# BSK4new.net
KiCad netlist of a schematic drawn in EAGLE
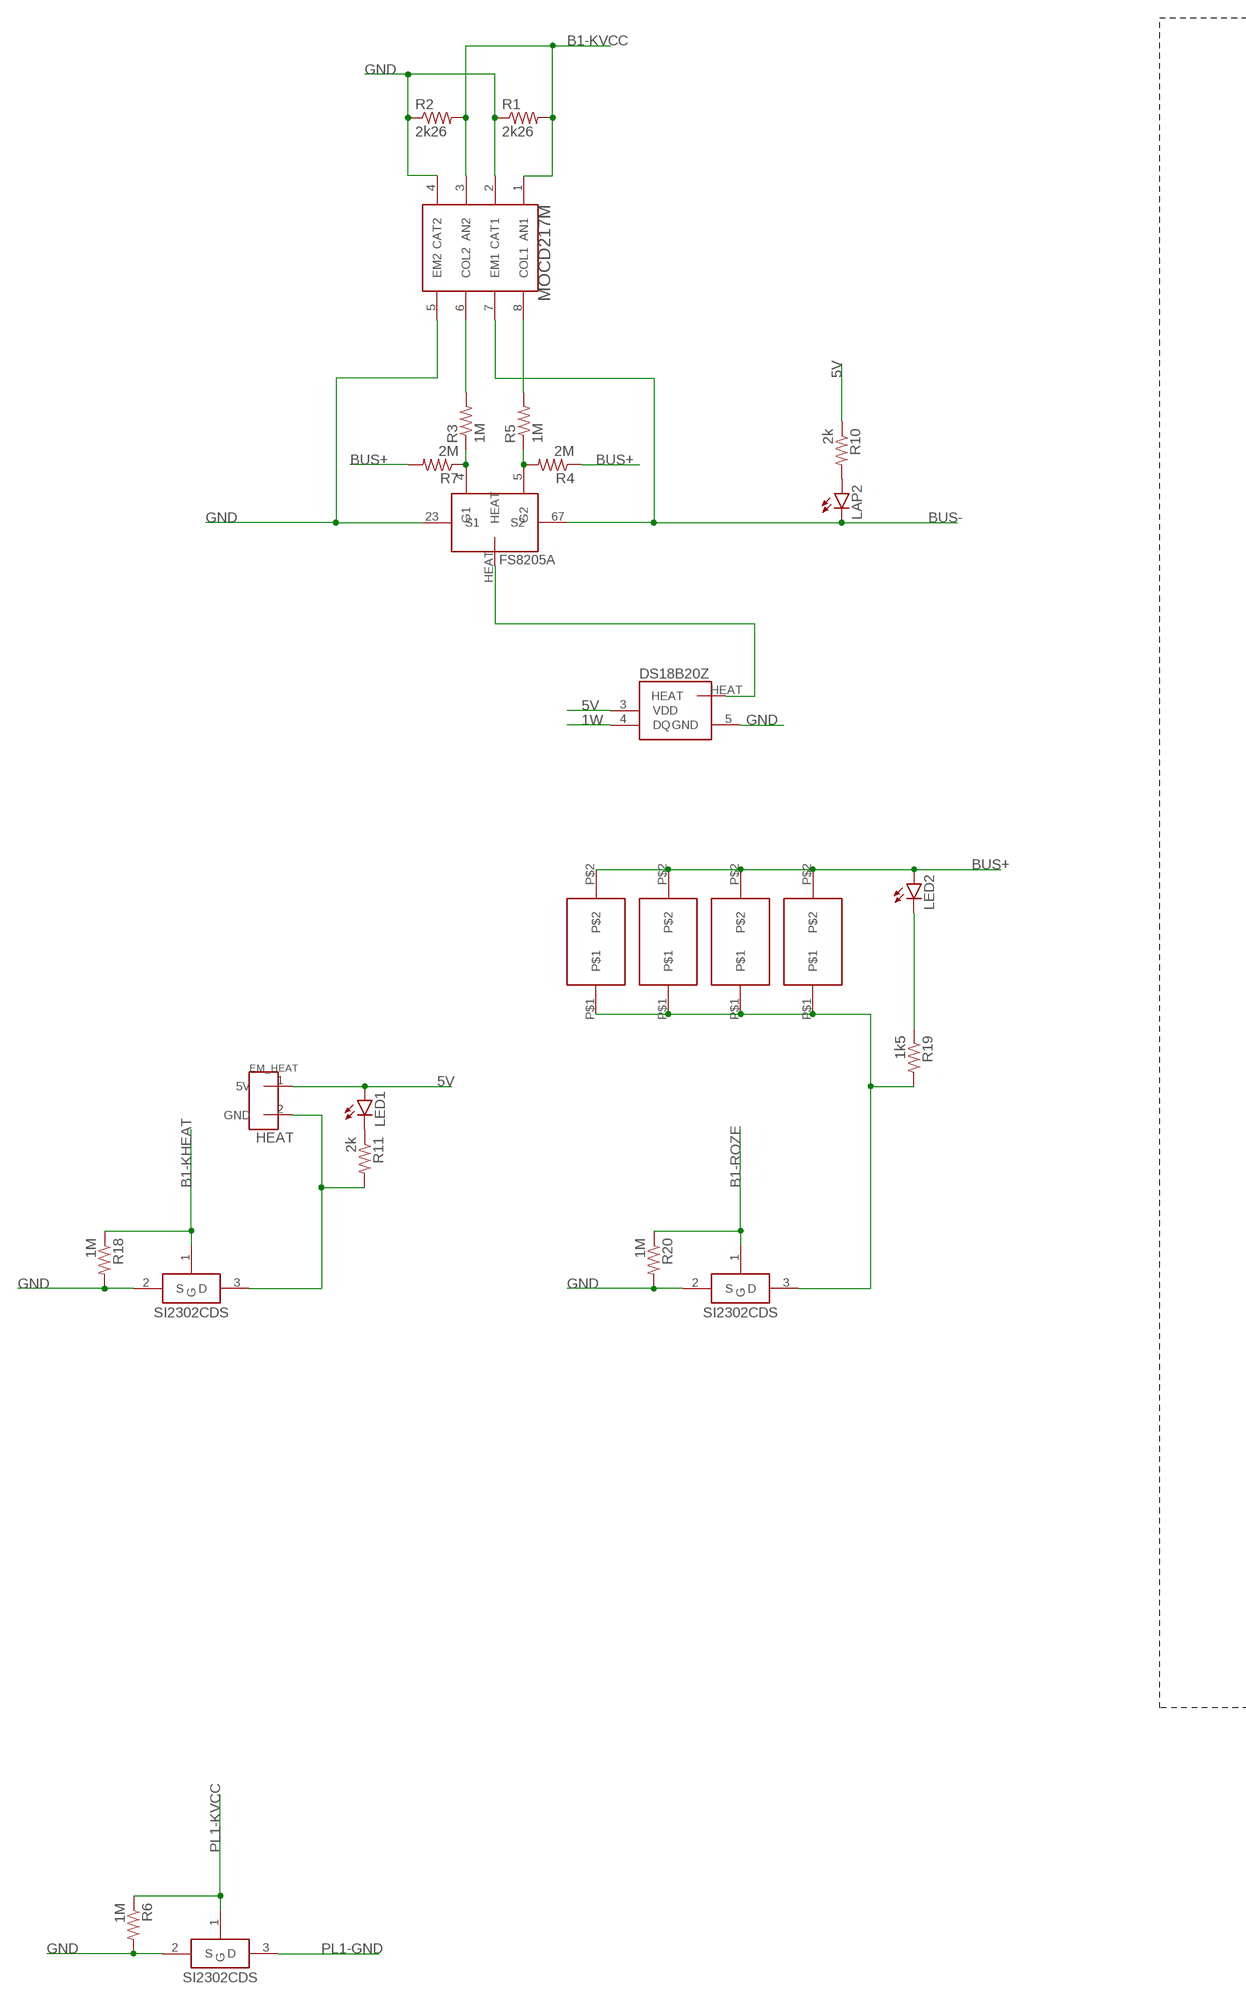
[diagram p0: schematic, sheet 1, part 1 of 2]
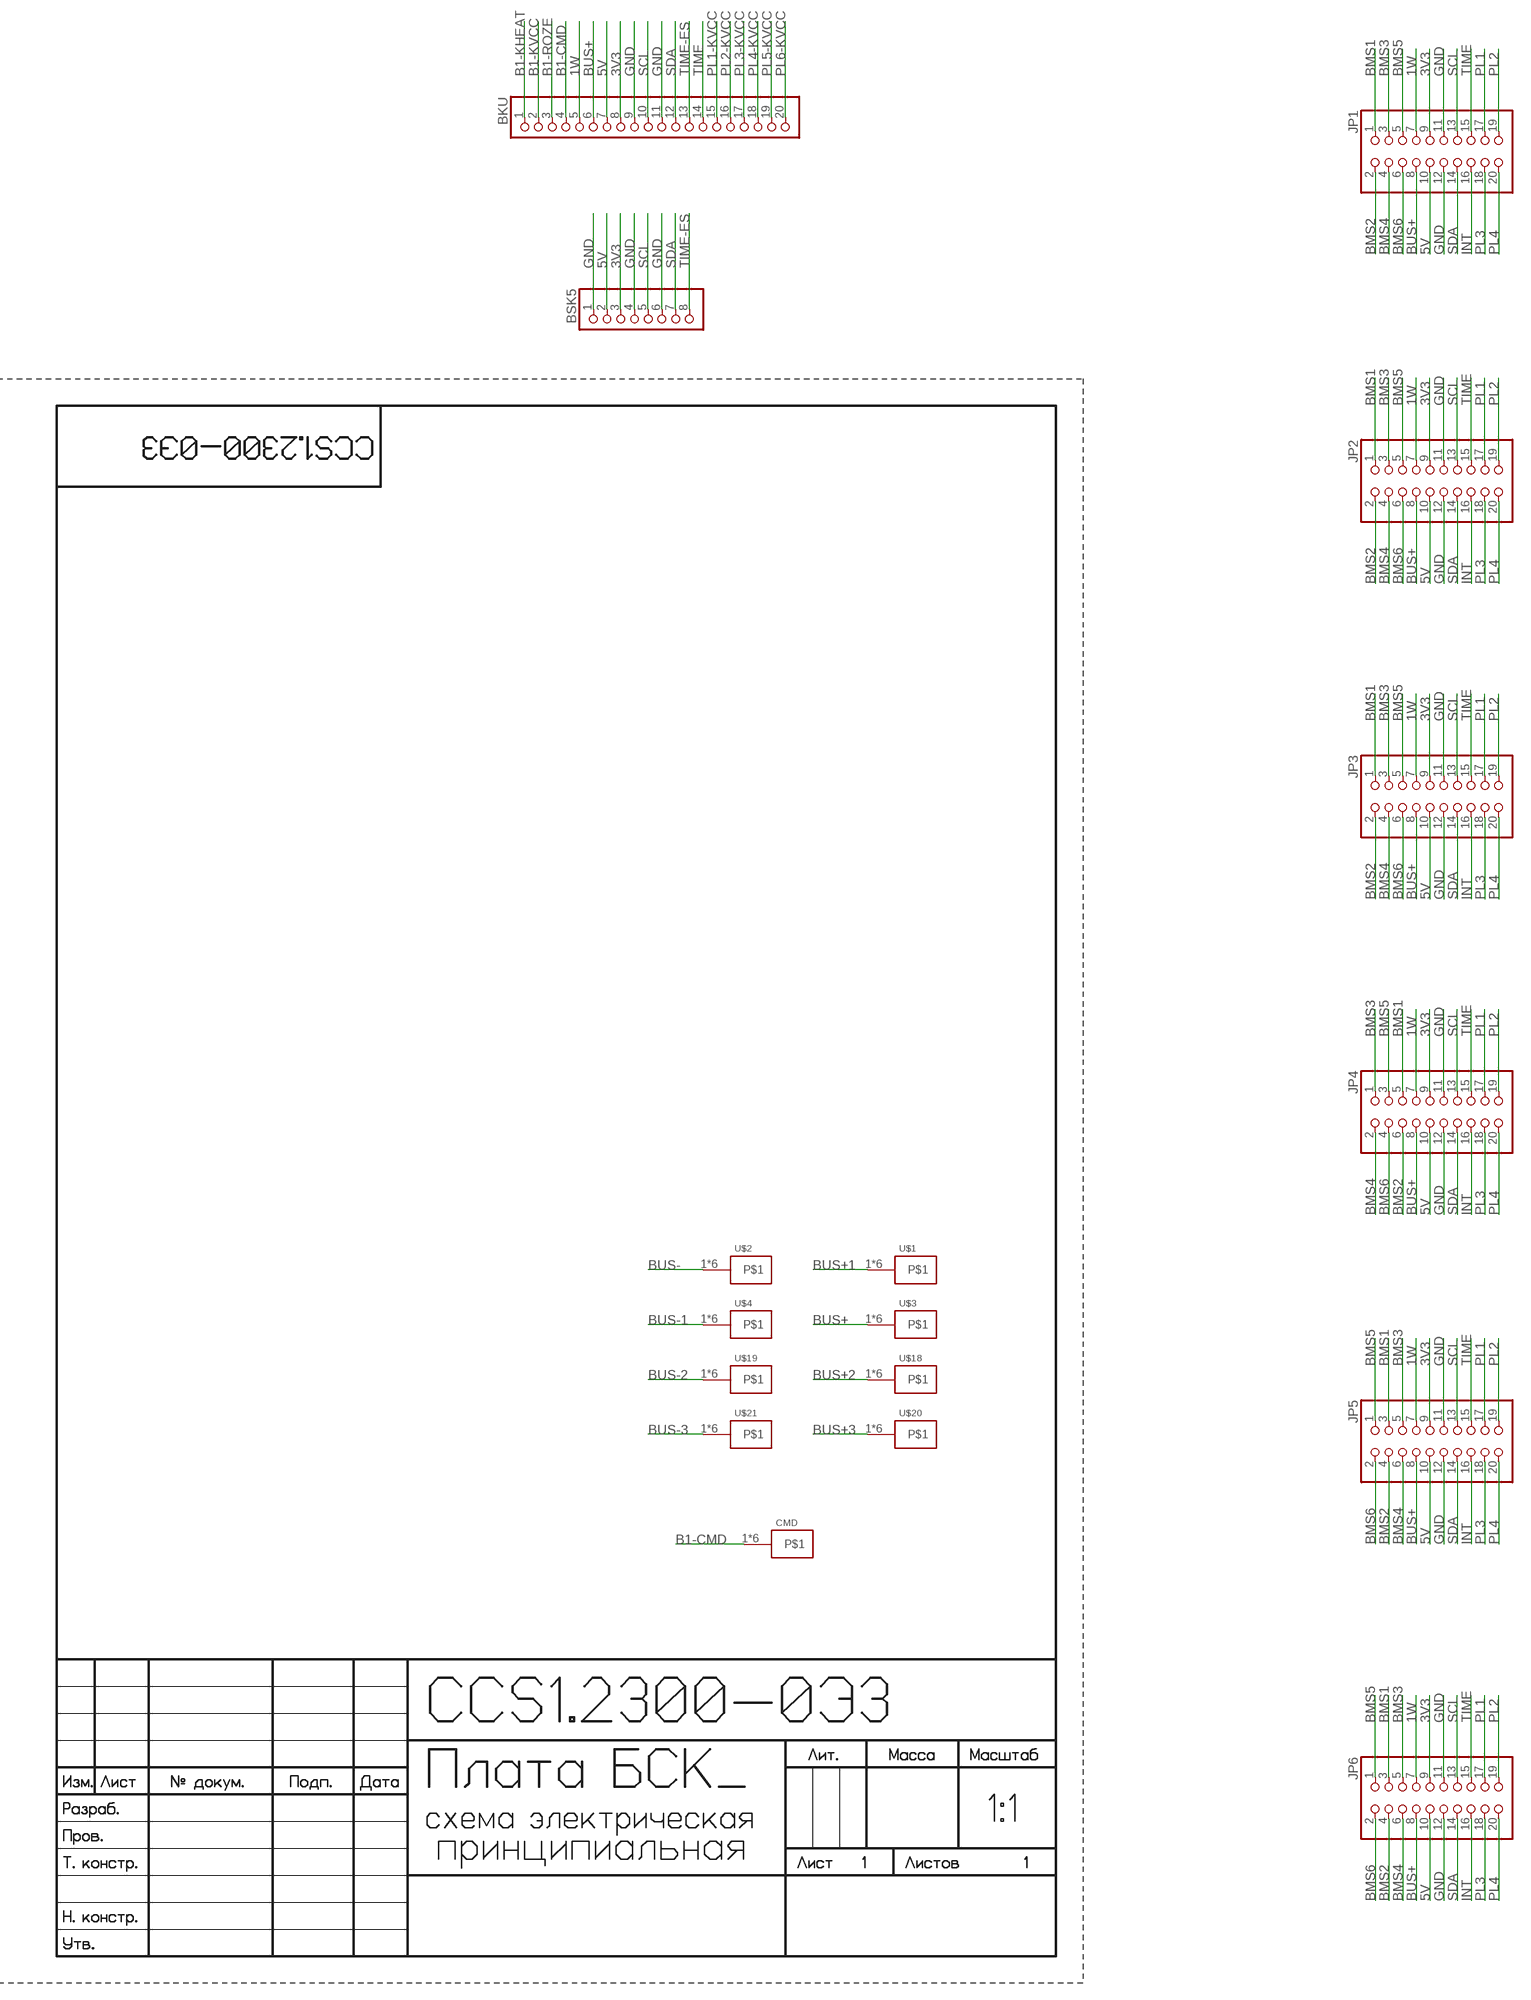
[diagram p1: schematic, sheet 1, part 2 of 2]

(export (version "E")
  (design (tool "Eeschema 10.0.6"))
  (components
    (comp (ref "BKU")
      (value "PINHD-1X20")
      (footprint "eagle-import:1X20")
      (libsource (lib "eagle-import") (part "PINHD-1X20"))
    )
    (comp (ref "BSK5")
      (value "PINHD-1X8")
      (footprint "eagle-import:1X08")
      (libsource (lib "eagle-import") (part "PINHD-1X8"))
    )
    (comp (ref "CMD")
      (value "KCONNECTQUAD")
      (footprint "eagle-import:KCONNECT_QUAD")
      (libsource (lib "eagle-import") (part "KCONNECTQUAD"))
    )
    (comp (ref "DS18B20Z")
      (value "DS18B20Z")
      (footprint "eagle-import:DS18B20Z")
      (libsource (lib "eagle-import") (part "DS18B20Z"))
    )
    (comp (ref "JP1")
      (value "PINHD-2X10")
      (footprint "eagle-import:2X10")
      (libsource (lib "eagle-import") (part "PINHD-2X10"))
    )
    (comp (ref "JP2")
      (value "PINHD-2X10")
      (footprint "eagle-import:2X10")
      (libsource (lib "eagle-import") (part "PINHD-2X10"))
    )
    (comp (ref "JP3")
      (value "PINHD-2X10")
      (footprint "eagle-import:2X10")
      (libsource (lib "eagle-import") (part "PINHD-2X10"))
    )
    (comp (ref "JP4")
      (value "PINHD-2X10")
      (footprint "eagle-import:2X10")
      (libsource (lib "eagle-import") (part "PINHD-2X10"))
    )
    (comp (ref "JP5")
      (value "PINHD-2X10")
      (footprint "eagle-import:2X10")
      (libsource (lib "eagle-import") (part "PINHD-2X10"))
    )
    (comp (ref "JP6")
      (value "PINHD-2X10")
      (footprint "eagle-import:2X10")
      (libsource (lib "eagle-import") (part "PINHD-2X10"))
    )
    (comp (ref "LAP2")
      (value "LAP4-BOTTOM")
      (footprint "eagle-import:P47F-BOTTOM")
      (libsource (lib "eagle-import") (part "P4-BOTTOMLA"))
    )
    (comp (ref "LED1")
      (value "LEDCHIPLED_0603")
      (footprint "eagle-import:CHIPLED_0603")
      (libsource (lib "eagle-import") (part "LEDCHIPLED_0603"))
    )
    (comp (ref "LED2")
      (value "LEDCHIPLED_0603")
      (footprint "eagle-import:CHIPLED_0603")
      (libsource (lib "eagle-import") (part "LEDCHIPLED_0603"))
    )
    (comp (ref "R1")
      (value "2k26")
      (footprint "eagle-import:R0603")
      (libsource (lib "eagle-import") (part "R-US_R0603"))
    )
    (comp (ref "R2")
      (value "2k26")
      (footprint "eagle-import:R0603")
      (libsource (lib "eagle-import") (part "R-US_R0603"))
    )
    (comp (ref "R3")
      (value "1M")
      (footprint "eagle-import:R0603")
      (libsource (lib "eagle-import") (part "R-US_R0603"))
    )
    (comp (ref "R4")
      (value "2M")
      (footprint "eagle-import:R0603")
      (libsource (lib "eagle-import") (part "R-US_R0603"))
    )
    (comp (ref "R5")
      (value "1M")
      (footprint "eagle-import:R0603")
      (libsource (lib "eagle-import") (part "R-US_R0603"))
    )
    (comp (ref "R6")
      (value "1M")
      (footprint "eagle-import:R0603")
      (libsource (lib "eagle-import") (part "R-US_R0603"))
    )
    (comp (ref "R7")
      (value "2M")
      (footprint "eagle-import:R0603")
      (libsource (lib "eagle-import") (part "R-US_R0603"))
    )
    (comp (ref "R10")
      (value "2k")
      (footprint "eagle-import:R0603")
      (libsource (lib "eagle-import") (part "R-US_R0603"))
    )
    (comp (ref "R11")
      (value "2k")
      (footprint "eagle-import:R0603")
      (libsource (lib "eagle-import") (part "R-US_R0603"))
    )
    (comp (ref "R18")
      (value "1M")
      (footprint "eagle-import:R0603")
      (libsource (lib "eagle-import") (part "R-US_R0603"))
    )
    (comp (ref "R19")
      (value "1k5")
      (footprint "eagle-import:R0603")
      (libsource (lib "eagle-import") (part "R-US_R0603"))
    )
    (comp (ref "R20")
      (value "1M")
      (footprint "eagle-import:R0603")
      (libsource (lib "eagle-import") (part "R-US_R0603"))
    )
    (comp (ref "U$1")
      (value "KCONNECT")
      (footprint "eagle-import:KCONNECT")
      (libsource (lib "eagle-import") (part "KCONNECT"))
    )
    (comp (ref "U$2")
      (value "KCONNECT")
      (footprint "eagle-import:KCONNECT")
      (libsource (lib "eagle-import") (part "KCONNECT"))
    )
    (comp (ref "U$3")
      (value "KCONNECT")
      (footprint "eagle-import:KCONNECT")
      (libsource (lib "eagle-import") (part "KCONNECT"))
    )
    (comp (ref "U$4")
      (value "KCONNECT")
      (footprint "eagle-import:KCONNECT")
      (libsource (lib "eagle-import") (part "KCONNECT"))
    )
    (comp (ref "U$5")
      (value "SI2302CDS")
      (footprint "eagle-import:SOT23-3")
      (libsource (lib "eagle-import") (part "SI2302CDS"))
    )
    (comp (ref "U$17")
      (value "FS8205A+")
      (footprint "eagle-import:FS8205A+")
      (libsource (lib "eagle-import") (part "FS8205A+"))
    )
    (comp (ref "U$18")
      (value "KCONNECT")
      (footprint "eagle-import:KCONNECT")
      (libsource (lib "eagle-import") (part "KCONNECT"))
    )
    (comp (ref "U$19")
      (value "KCONNECT")
      (footprint "eagle-import:KCONNECT")
      (libsource (lib "eagle-import") (part "KCONNECT"))
    )
    (comp (ref "U$20")
      (value "KCONNECT")
      (footprint "eagle-import:KCONNECT")
      (libsource (lib "eagle-import") (part "KCONNECT"))
    )
    (comp (ref "U$21")
      (value "KCONNECT")
      (footprint "eagle-import:KCONNECT")
      (libsource (lib "eagle-import") (part "KCONNECT"))
    )
    (comp (ref "U$22")
      (value "MOCD217M")
      (footprint "eagle-import:SOIC8")
      (libsource (lib "eagle-import") (part "MOCD217M"))
    )
    (comp (ref "U$23")
      (value "SI2302CDS")
      (footprint "eagle-import:SOT23-3")
      (libsource (lib "eagle-import") (part "SI2302CDS"))
    )
    (comp (ref "U$24")
      (value "EM_HEAT")
      (footprint "eagle-import:EM_HEAT")
      (libsource (lib "eagle-import") (part "EM_HEAT"))
    )
    (comp (ref "U$25")
      (value "SI2302CDS")
      (footprint "eagle-import:SOT23-3")
      (libsource (lib "eagle-import") (part "SI2302CDS"))
    )
    (comp (ref "U$27")
      (value "GRAFITGRAFIT3_1")
      (footprint "eagle-import:GRAFIT3_1")
      (libsource (lib "eagle-import") (part "GRAFITGRAFIT3_1"))
    )
    (comp (ref "U$28")
      (value "GRAFITGRAFIT3_1")
      (footprint "eagle-import:GRAFIT3_1")
      (libsource (lib "eagle-import") (part "GRAFITGRAFIT3_1"))
    )
    (comp (ref "U$29")
      (value "GRAFITGRAFIT3_1")
      (footprint "eagle-import:GRAFIT3_1")
      (libsource (lib "eagle-import") (part "GRAFITGRAFIT3_1"))
    )
    (comp (ref "U$30")
      (value "GRAFITGRAFIT3_1")
      (footprint "eagle-import:GRAFIT3_1")
      (libsource (lib "eagle-import") (part "GRAFITGRAFIT3_1"))
    )
  )
  (nets
    (net (code "1") (name "/1W") (class "Default")
      (node (ref "BKU") (pin "5") (pinfunction "5_5") (pintype "passive"))
      (node (ref "DS18B20Z") (pin "4") (pinfunction "DQ_4") (pintype "bidirectional"))
      (node (ref "JP1") (pin "7") (pinfunction "7_7") (pintype "passive"))
      (node (ref "JP2") (pin "7") (pinfunction "7_7") (pintype "passive"))
      (node (ref "JP3") (pin "7") (pinfunction "7_7") (pintype "passive"))
      (node (ref "JP4") (pin "7") (pinfunction "7_7") (pintype "passive"))
      (node (ref "JP5") (pin "7") (pinfunction "7_7") (pintype "passive"))
      (node (ref "JP6") (pin "7") (pinfunction "7_7") (pintype "passive"))
    )
    (net (code "2") (name "/3V3") (class "Default")
      (node (ref "BKU") (pin "8") (pinfunction "8_8") (pintype "passive"))
      (node (ref "BSK5") (pin "3") (pinfunction "3_3") (pintype "passive"))
      (node (ref "JP1") (pin "9") (pinfunction "9_9") (pintype "passive"))
      (node (ref "JP2") (pin "9") (pinfunction "9_9") (pintype "passive"))
      (node (ref "JP3") (pin "9") (pinfunction "9_9") (pintype "passive"))
      (node (ref "JP4") (pin "9") (pinfunction "9_9") (pintype "passive"))
      (node (ref "JP5") (pin "9") (pinfunction "9_9") (pintype "passive"))
      (node (ref "JP6") (pin "9") (pinfunction "9_9") (pintype "passive"))
    )
    (net (code "3") (name "/5V") (class "Default")
      (node (ref "BKU") (pin "7") (pinfunction "7_7") (pintype "passive"))
      (node (ref "BSK5") (pin "2") (pinfunction "2_2") (pintype "passive"))
      (node (ref "DS18B20Z") (pin "3") (pinfunction "VDD_3") (pintype "bidirectional"))
      (node (ref "JP1") (pin "10") (pinfunction "10_10") (pintype "passive"))
      (node (ref "JP2") (pin "10") (pinfunction "10_10") (pintype "passive"))
      (node (ref "JP3") (pin "10") (pinfunction "10_10") (pintype "passive"))
      (node (ref "JP4") (pin "10") (pinfunction "10_10") (pintype "passive"))
      (node (ref "JP5") (pin "10") (pinfunction "10_10") (pintype "passive"))
      (node (ref "JP6") (pin "10") (pinfunction "10_10") (pintype "passive"))
      (node (ref "LED1") (pin "A") (pinfunction "A_A") (pintype "passive"))
      (node (ref "R10") (pin "1") (pinfunction "1_1") (pintype "passive"))
      (node (ref "U$24") (pin "1") (pinfunction "5V_1") (pintype "bidirectional"))
    )
    (net (code "4") (name "/B1-CMD") (class "Default")
      (node (ref "BKU") (pin "4") (pinfunction "4_4") (pintype "passive"))
      (node (ref "CMD") (pin "1") (pinfunction "P$1_1") (pintype "bidirectional"))
      (node (ref "CMD") (pin "2") (pinfunction "P$1_2") (pintype "bidirectional"))
      (node (ref "CMD") (pin "3") (pinfunction "P$1_3") (pintype "bidirectional"))
      (node (ref "CMD") (pin "4") (pinfunction "P$1_4") (pintype "bidirectional"))
      (node (ref "CMD") (pin "P$1") (pinfunction "P$1_P$1") (pintype "bidirectional"))
      (node (ref "CMD") (pin "P$2") (pinfunction "P$1_P$2") (pintype "bidirectional"))
    )
    (net (code "5") (name "/B1-KHEAT") (class "Default")
      (node (ref "BKU") (pin "1") (pinfunction "1_1") (pintype "passive"))
      (node (ref "R18") (pin "1") (pinfunction "1_1") (pintype "passive"))
      (node (ref "U$23") (pin "1") (pinfunction "G_1") (pintype "bidirectional"))
    )
    (net (code "6") (name "/B1-KVCC") (class "Default")
      (node (ref "BKU") (pin "2") (pinfunction "2_2") (pintype "passive"))
      (node (ref "R1") (pin "2") (pinfunction "2_2") (pintype "passive"))
      (node (ref "R2") (pin "2") (pinfunction "2_2") (pintype "passive"))
      (node (ref "U$22") (pin "1") (pinfunction "AN1_1") (pintype "bidirectional"))
      (node (ref "U$22") (pin "3") (pinfunction "AN2_3") (pintype "bidirectional"))
    )
    (net (code "7") (name "/B1-ROZE") (class "Default")
      (node (ref "BKU") (pin "3") (pinfunction "3_3") (pintype "passive"))
      (node (ref "R20") (pin "1") (pinfunction "1_1") (pintype "passive"))
      (node (ref "U$25") (pin "1") (pinfunction "G_1") (pintype "bidirectional"))
    )
    (net (code "8") (name "/BMS1") (class "Default")
      (node (ref "JP1") (pin "1") (pinfunction "1_1") (pintype "passive"))
      (node (ref "JP2") (pin "1") (pinfunction "1_1") (pintype "passive"))
      (node (ref "JP3") (pin "1") (pinfunction "1_1") (pintype "passive"))
      (node (ref "JP4") (pin "5") (pinfunction "5_5") (pintype "passive"))
      (node (ref "JP5") (pin "3") (pinfunction "3_3") (pintype "passive"))
      (node (ref "JP6") (pin "3") (pinfunction "3_3") (pintype "passive"))
    )
    (net (code "9") (name "/BMS2") (class "Default")
      (node (ref "JP1") (pin "2") (pinfunction "2_2") (pintype "passive"))
      (node (ref "JP2") (pin "2") (pinfunction "2_2") (pintype "passive"))
      (node (ref "JP3") (pin "2") (pinfunction "2_2") (pintype "passive"))
      (node (ref "JP4") (pin "6") (pinfunction "6_6") (pintype "passive"))
      (node (ref "JP5") (pin "4") (pinfunction "4_4") (pintype "passive"))
      (node (ref "JP6") (pin "4") (pinfunction "4_4") (pintype "passive"))
    )
    (net (code "10") (name "/BMS3") (class "Default")
      (node (ref "JP1") (pin "3") (pinfunction "3_3") (pintype "passive"))
      (node (ref "JP2") (pin "3") (pinfunction "3_3") (pintype "passive"))
      (node (ref "JP3") (pin "3") (pinfunction "3_3") (pintype "passive"))
      (node (ref "JP4") (pin "1") (pinfunction "1_1") (pintype "passive"))
      (node (ref "JP5") (pin "5") (pinfunction "5_5") (pintype "passive"))
      (node (ref "JP6") (pin "5") (pinfunction "5_5") (pintype "passive"))
    )
    (net (code "11") (name "/BMS4") (class "Default")
      (node (ref "JP1") (pin "4") (pinfunction "4_4") (pintype "passive"))
      (node (ref "JP2") (pin "4") (pinfunction "4_4") (pintype "passive"))
      (node (ref "JP3") (pin "4") (pinfunction "4_4") (pintype "passive"))
      (node (ref "JP4") (pin "2") (pinfunction "2_2") (pintype "passive"))
      (node (ref "JP5") (pin "6") (pinfunction "6_6") (pintype "passive"))
      (node (ref "JP6") (pin "6") (pinfunction "6_6") (pintype "passive"))
    )
    (net (code "12") (name "/BMS5") (class "Default")
      (node (ref "JP1") (pin "5") (pinfunction "5_5") (pintype "passive"))
      (node (ref "JP2") (pin "5") (pinfunction "5_5") (pintype "passive"))
      (node (ref "JP3") (pin "5") (pinfunction "5_5") (pintype "passive"))
      (node (ref "JP4") (pin "3") (pinfunction "3_3") (pintype "passive"))
      (node (ref "JP5") (pin "1") (pinfunction "1_1") (pintype "passive"))
      (node (ref "JP6") (pin "1") (pinfunction "1_1") (pintype "passive"))
    )
    (net (code "13") (name "/BMS6") (class "Default")
      (node (ref "JP1") (pin "6") (pinfunction "6_6") (pintype "passive"))
      (node (ref "JP2") (pin "6") (pinfunction "6_6") (pintype "passive"))
      (node (ref "JP3") (pin "6") (pinfunction "6_6") (pintype "passive"))
      (node (ref "JP4") (pin "4") (pinfunction "4_4") (pintype "passive"))
      (node (ref "JP5") (pin "2") (pinfunction "2_2") (pintype "passive"))
      (node (ref "JP6") (pin "2") (pinfunction "2_2") (pintype "passive"))
    )
    (net (code "14") (name "/BUS+") (class "Default")
      (node (ref "BKU") (pin "6") (pinfunction "6_6") (pintype "passive"))
      (node (ref "JP1") (pin "8") (pinfunction "8_8") (pintype "passive"))
      (node (ref "JP2") (pin "8") (pinfunction "8_8") (pintype "passive"))
      (node (ref "JP3") (pin "8") (pinfunction "8_8") (pintype "passive"))
      (node (ref "JP4") (pin "8") (pinfunction "8_8") (pintype "passive"))
      (node (ref "JP5") (pin "8") (pinfunction "8_8") (pintype "passive"))
      (node (ref "JP6") (pin "8") (pinfunction "8_8") (pintype "passive"))
      (node (ref "LED2") (pin "A") (pinfunction "A_A") (pintype "passive"))
      (node (ref "R4") (pin "1") (pinfunction "1_1") (pintype "passive"))
      (node (ref "R7") (pin "2") (pinfunction "2_2") (pintype "passive"))
      (node (ref "U$27") (pin "P$2") (pinfunction "P$2_P$2") (pintype "bidirectional"))
      (node (ref "U$28") (pin "P$2") (pinfunction "P$2_P$2") (pintype "bidirectional"))
      (node (ref "U$29") (pin "P$2") (pinfunction "P$2_P$2") (pintype "bidirectional"))
      (node (ref "U$3") (pin "1") (pinfunction "P$1_1") (pintype "bidirectional"))
      (node (ref "U$3") (pin "2") (pinfunction "P$1_2") (pintype "bidirectional"))
      (node (ref "U$3") (pin "3") (pinfunction "P$1_3") (pintype "bidirectional"))
      (node (ref "U$3") (pin "4") (pinfunction "P$1_4") (pintype "bidirectional"))
      (node (ref "U$3") (pin "P$1") (pinfunction "P$1_P$1") (pintype "bidirectional"))
      (node (ref "U$3") (pin "P$2") (pinfunction "P$1_P$2") (pintype "bidirectional"))
      (node (ref "U$30") (pin "P$2") (pinfunction "P$2_P$2") (pintype "bidirectional"))
    )
    (net (code "15") (name "/BUS+1") (class "Default")
      (node (ref "U$1") (pin "1") (pinfunction "P$1_1") (pintype "bidirectional"))
      (node (ref "U$1") (pin "2") (pinfunction "P$1_2") (pintype "bidirectional"))
      (node (ref "U$1") (pin "3") (pinfunction "P$1_3") (pintype "bidirectional"))
      (node (ref "U$1") (pin "4") (pinfunction "P$1_4") (pintype "bidirectional"))
      (node (ref "U$1") (pin "P$1") (pinfunction "P$1_P$1") (pintype "bidirectional"))
      (node (ref "U$1") (pin "P$2") (pinfunction "P$1_P$2") (pintype "bidirectional"))
    )
    (net (code "16") (name "/BUS+2") (class "Default")
      (node (ref "U$18") (pin "1") (pinfunction "P$1_1") (pintype "bidirectional"))
      (node (ref "U$18") (pin "2") (pinfunction "P$1_2") (pintype "bidirectional"))
      (node (ref "U$18") (pin "3") (pinfunction "P$1_3") (pintype "bidirectional"))
      (node (ref "U$18") (pin "4") (pinfunction "P$1_4") (pintype "bidirectional"))
      (node (ref "U$18") (pin "P$1") (pinfunction "P$1_P$1") (pintype "bidirectional"))
      (node (ref "U$18") (pin "P$2") (pinfunction "P$1_P$2") (pintype "bidirectional"))
    )
    (net (code "17") (name "/BUS+3") (class "Default")
      (node (ref "U$20") (pin "1") (pinfunction "P$1_1") (pintype "bidirectional"))
      (node (ref "U$20") (pin "2") (pinfunction "P$1_2") (pintype "bidirectional"))
      (node (ref "U$20") (pin "3") (pinfunction "P$1_3") (pintype "bidirectional"))
      (node (ref "U$20") (pin "4") (pinfunction "P$1_4") (pintype "bidirectional"))
      (node (ref "U$20") (pin "P$1") (pinfunction "P$1_P$1") (pintype "bidirectional"))
      (node (ref "U$20") (pin "P$2") (pinfunction "P$1_P$2") (pintype "bidirectional"))
    )
    (net (code "18") (name "/BUS-") (class "Default")
      (node (ref "LAP2") (pin "C") (pinfunction "C_C") (pintype "passive"))
      (node (ref "U$17") (pin "67") (pinfunction "S2_67") (pintype "bidirectional"))
      (node (ref "U$2") (pin "1") (pinfunction "P$1_1") (pintype "bidirectional"))
      (node (ref "U$2") (pin "2") (pinfunction "P$1_2") (pintype "bidirectional"))
      (node (ref "U$2") (pin "3") (pinfunction "P$1_3") (pintype "bidirectional"))
      (node (ref "U$2") (pin "4") (pinfunction "P$1_4") (pintype "bidirectional"))
      (node (ref "U$2") (pin "P$1") (pinfunction "P$1_P$1") (pintype "bidirectional"))
      (node (ref "U$2") (pin "P$2") (pinfunction "P$1_P$2") (pintype "bidirectional"))
      (node (ref "U$22") (pin "7") (pinfunction "EM1_7") (pintype "bidirectional"))
    )
    (net (code "19") (name "/BUS-1") (class "Default")
      (node (ref "U$4") (pin "1") (pinfunction "P$1_1") (pintype "bidirectional"))
      (node (ref "U$4") (pin "2") (pinfunction "P$1_2") (pintype "bidirectional"))
      (node (ref "U$4") (pin "3") (pinfunction "P$1_3") (pintype "bidirectional"))
      (node (ref "U$4") (pin "4") (pinfunction "P$1_4") (pintype "bidirectional"))
      (node (ref "U$4") (pin "P$1") (pinfunction "P$1_P$1") (pintype "bidirectional"))
      (node (ref "U$4") (pin "P$2") (pinfunction "P$1_P$2") (pintype "bidirectional"))
    )
    (net (code "20") (name "/BUS-2") (class "Default")
      (node (ref "U$19") (pin "1") (pinfunction "P$1_1") (pintype "bidirectional"))
      (node (ref "U$19") (pin "2") (pinfunction "P$1_2") (pintype "bidirectional"))
      (node (ref "U$19") (pin "3") (pinfunction "P$1_3") (pintype "bidirectional"))
      (node (ref "U$19") (pin "4") (pinfunction "P$1_4") (pintype "bidirectional"))
      (node (ref "U$19") (pin "P$1") (pinfunction "P$1_P$1") (pintype "bidirectional"))
      (node (ref "U$19") (pin "P$2") (pinfunction "P$1_P$2") (pintype "bidirectional"))
    )
    (net (code "21") (name "/BUS-3") (class "Default")
      (node (ref "U$21") (pin "1") (pinfunction "P$1_1") (pintype "bidirectional"))
      (node (ref "U$21") (pin "2") (pinfunction "P$1_2") (pintype "bidirectional"))
      (node (ref "U$21") (pin "3") (pinfunction "P$1_3") (pintype "bidirectional"))
      (node (ref "U$21") (pin "4") (pinfunction "P$1_4") (pintype "bidirectional"))
      (node (ref "U$21") (pin "P$1") (pinfunction "P$1_P$1") (pintype "bidirectional"))
      (node (ref "U$21") (pin "P$2") (pinfunction "P$1_P$2") (pintype "bidirectional"))
    )
    (net (code "22") (name "/GND") (class "Default")
      (node (ref "BKU") (pin "11") (pinfunction "11_11") (pintype "passive"))
      (node (ref "BKU") (pin "9") (pinfunction "9_9") (pintype "passive"))
      (node (ref "BSK5") (pin "1") (pinfunction "1_1") (pintype "passive"))
      (node (ref "BSK5") (pin "4") (pinfunction "4_4") (pintype "passive"))
      (node (ref "BSK5") (pin "6") (pinfunction "6_6") (pintype "passive"))
      (node (ref "DS18B20Z") (pin "5") (pinfunction "GND_5") (pintype "bidirectional"))
      (node (ref "JP1") (pin "11") (pinfunction "11_11") (pintype "passive"))
      (node (ref "JP1") (pin "12") (pinfunction "12_12") (pintype "passive"))
      (node (ref "JP2") (pin "11") (pinfunction "11_11") (pintype "passive"))
      (node (ref "JP2") (pin "12") (pinfunction "12_12") (pintype "passive"))
      (node (ref "JP3") (pin "11") (pinfunction "11_11") (pintype "passive"))
      (node (ref "JP3") (pin "12") (pinfunction "12_12") (pintype "passive"))
      (node (ref "JP4") (pin "11") (pinfunction "11_11") (pintype "passive"))
      (node (ref "JP4") (pin "12") (pinfunction "12_12") (pintype "passive"))
      (node (ref "JP5") (pin "11") (pinfunction "11_11") (pintype "passive"))
      (node (ref "JP5") (pin "12") (pinfunction "12_12") (pintype "passive"))
      (node (ref "JP6") (pin "11") (pinfunction "11_11") (pintype "passive"))
      (node (ref "JP6") (pin "12") (pinfunction "12_12") (pintype "passive"))
      (node (ref "R1") (pin "1") (pinfunction "1_1") (pintype "passive"))
      (node (ref "R18") (pin "2") (pinfunction "2_2") (pintype "passive"))
      (node (ref "R2") (pin "1") (pinfunction "1_1") (pintype "passive"))
      (node (ref "R20") (pin "2") (pinfunction "2_2") (pintype "passive"))
      (node (ref "R6") (pin "2") (pinfunction "2_2") (pintype "passive"))
      (node (ref "U$17") (pin "23") (pinfunction "S1_23") (pintype "bidirectional"))
      (node (ref "U$22") (pin "2") (pinfunction "CAT1_2") (pintype "bidirectional"))
      (node (ref "U$22") (pin "4") (pinfunction "CAT2_4") (pintype "bidirectional"))
      (node (ref "U$22") (pin "5") (pinfunction "EM2_5") (pintype "bidirectional"))
      (node (ref "U$23") (pin "2") (pinfunction "S_2") (pintype "bidirectional"))
      (node (ref "U$25") (pin "2") (pinfunction "S_2") (pintype "bidirectional"))
      (node (ref "U$5") (pin "2") (pinfunction "S_2") (pintype "bidirectional"))
    )
    (net (code "23") (name "/INT") (class "Default")
      (node (ref "JP1") (pin "16") (pinfunction "16_16") (pintype "passive"))
      (node (ref "JP2") (pin "16") (pinfunction "16_16") (pintype "passive"))
      (node (ref "JP3") (pin "16") (pinfunction "16_16") (pintype "passive"))
      (node (ref "JP4") (pin "16") (pinfunction "16_16") (pintype "passive"))
      (node (ref "JP5") (pin "16") (pinfunction "16_16") (pintype "passive"))
      (node (ref "JP6") (pin "16") (pinfunction "16_16") (pintype "passive"))
    )
    (net (code "24") (name "/PL1") (class "Default")
      (node (ref "JP1") (pin "17") (pinfunction "17_17") (pintype "passive"))
      (node (ref "JP2") (pin "17") (pinfunction "17_17") (pintype "passive"))
      (node (ref "JP3") (pin "17") (pinfunction "17_17") (pintype "passive"))
      (node (ref "JP4") (pin "17") (pinfunction "17_17") (pintype "passive"))
      (node (ref "JP5") (pin "17") (pinfunction "17_17") (pintype "passive"))
      (node (ref "JP6") (pin "17") (pinfunction "17_17") (pintype "passive"))
    )
    (net (code "25") (name "/PL1-GND") (class "Default")
      (node (ref "U$5") (pin "3") (pinfunction "D_3") (pintype "bidirectional"))
    )
    (net (code "26") (name "/PL1-KVCC") (class "Default")
      (node (ref "BKU") (pin "15") (pinfunction "15_15") (pintype "passive"))
      (node (ref "R6") (pin "1") (pinfunction "1_1") (pintype "passive"))
      (node (ref "U$5") (pin "1") (pinfunction "G_1") (pintype "bidirectional"))
    )
    (net (code "27") (name "/PL2") (class "Default")
      (node (ref "JP1") (pin "19") (pinfunction "19_19") (pintype "passive"))
      (node (ref "JP2") (pin "19") (pinfunction "19_19") (pintype "passive"))
      (node (ref "JP3") (pin "19") (pinfunction "19_19") (pintype "passive"))
      (node (ref "JP4") (pin "19") (pinfunction "19_19") (pintype "passive"))
      (node (ref "JP5") (pin "19") (pinfunction "19_19") (pintype "passive"))
      (node (ref "JP6") (pin "19") (pinfunction "19_19") (pintype "passive"))
    )
    (net (code "28") (name "/PL2-KVCC") (class "Default")
      (node (ref "BKU") (pin "16") (pinfunction "16_16") (pintype "passive"))
    )
    (net (code "29") (name "/PL3") (class "Default")
      (node (ref "JP1") (pin "18") (pinfunction "18_18") (pintype "passive"))
      (node (ref "JP2") (pin "18") (pinfunction "18_18") (pintype "passive"))
      (node (ref "JP3") (pin "18") (pinfunction "18_18") (pintype "passive"))
      (node (ref "JP4") (pin "18") (pinfunction "18_18") (pintype "passive"))
      (node (ref "JP5") (pin "18") (pinfunction "18_18") (pintype "passive"))
      (node (ref "JP6") (pin "18") (pinfunction "18_18") (pintype "passive"))
    )
    (net (code "30") (name "/PL3-KVCC") (class "Default")
      (node (ref "BKU") (pin "17") (pinfunction "17_17") (pintype "passive"))
    )
    (net (code "31") (name "/PL4") (class "Default")
      (node (ref "JP1") (pin "20") (pinfunction "20_20") (pintype "passive"))
      (node (ref "JP2") (pin "20") (pinfunction "20_20") (pintype "passive"))
      (node (ref "JP3") (pin "20") (pinfunction "20_20") (pintype "passive"))
      (node (ref "JP4") (pin "20") (pinfunction "20_20") (pintype "passive"))
      (node (ref "JP5") (pin "20") (pinfunction "20_20") (pintype "passive"))
      (node (ref "JP6") (pin "20") (pinfunction "20_20") (pintype "passive"))
    )
    (net (code "32") (name "/PL4-KVCC") (class "Default")
      (node (ref "BKU") (pin "18") (pinfunction "18_18") (pintype "passive"))
    )
    (net (code "33") (name "/PL5-KVCC") (class "Default")
      (node (ref "BKU") (pin "19") (pinfunction "19_19") (pintype "passive"))
    )
    (net (code "34") (name "/PL6-KVCC") (class "Default")
      (node (ref "BKU") (pin "20") (pinfunction "20_20") (pintype "passive"))
    )
    (net (code "35") (name "/SCL") (class "Default")
      (node (ref "BKU") (pin "10") (pinfunction "10_10") (pintype "passive"))
      (node (ref "BSK5") (pin "5") (pinfunction "5_5") (pintype "passive"))
      (node (ref "JP1") (pin "13") (pinfunction "13_13") (pintype "passive"))
      (node (ref "JP2") (pin "13") (pinfunction "13_13") (pintype "passive"))
      (node (ref "JP3") (pin "13") (pinfunction "13_13") (pintype "passive"))
      (node (ref "JP4") (pin "13") (pinfunction "13_13") (pintype "passive"))
      (node (ref "JP5") (pin "13") (pinfunction "13_13") (pintype "passive"))
      (node (ref "JP6") (pin "13") (pinfunction "13_13") (pintype "passive"))
    )
    (net (code "36") (name "/SDA") (class "Default")
      (node (ref "BKU") (pin "12") (pinfunction "12_12") (pintype "passive"))
      (node (ref "BSK5") (pin "7") (pinfunction "7_7") (pintype "passive"))
      (node (ref "JP1") (pin "14") (pinfunction "14_14") (pintype "passive"))
      (node (ref "JP2") (pin "14") (pinfunction "14_14") (pintype "passive"))
      (node (ref "JP3") (pin "14") (pinfunction "14_14") (pintype "passive"))
      (node (ref "JP4") (pin "14") (pinfunction "14_14") (pintype "passive"))
      (node (ref "JP5") (pin "14") (pinfunction "14_14") (pintype "passive"))
      (node (ref "JP6") (pin "14") (pinfunction "14_14") (pintype "passive"))
    )
    (net (code "37") (name "/TIME") (class "Default")
      (node (ref "BKU") (pin "14") (pinfunction "14_14") (pintype "passive"))
      (node (ref "JP1") (pin "15") (pinfunction "15_15") (pintype "passive"))
      (node (ref "JP2") (pin "15") (pinfunction "15_15") (pintype "passive"))
      (node (ref "JP3") (pin "15") (pinfunction "15_15") (pintype "passive"))
      (node (ref "JP4") (pin "15") (pinfunction "15_15") (pintype "passive"))
      (node (ref "JP5") (pin "15") (pinfunction "15_15") (pintype "passive"))
      (node (ref "JP6") (pin "15") (pinfunction "15_15") (pintype "passive"))
    )
    (net (code "38") (name "/TIME-ES") (class "Default")
      (node (ref "BKU") (pin "13") (pinfunction "13_13") (pintype "passive"))
      (node (ref "BSK5") (pin "8") (pinfunction "8_8") (pintype "passive"))
    )
    (net (code "39") (name "Net-(DS18B20Z-PadHEAT)") (class "Default")
      (node (ref "DS18B20Z") (pin "HEAT") (pinfunction "HEAT_HEAT") (pintype "bidirectional"))
      (node (ref "U$17") (pin "HEAT") (pinfunction "HEAT_HEAT") (pintype "bidirectional"))
    )
    (net (code "40") (name "Net-(LAP2-PadA)") (class "Default")
      (node (ref "LAP2") (pin "A") (pinfunction "A_A") (pintype "passive"))
      (node (ref "R10") (pin "2") (pinfunction "2_2") (pintype "passive"))
    )
    (net (code "41") (name "Net-(LED1-PadC)") (class "Default")
      (node (ref "LED1") (pin "C") (pinfunction "C_C") (pintype "passive"))
      (node (ref "R11") (pin "1") (pinfunction "1_1") (pintype "passive"))
    )
    (net (code "42") (name "Net-(LED2-PadC)") (class "Default")
      (node (ref "LED2") (pin "C") (pinfunction "C_C") (pintype "passive"))
      (node (ref "R19") (pin "1") (pinfunction "1_1") (pintype "passive"))
    )
    (net (code "43") (name "Net-(U$17-G1)") (class "Default")
      (node (ref "R3") (pin "1") (pinfunction "1_1") (pintype "passive"))
      (node (ref "R7") (pin "1") (pinfunction "1_1") (pintype "passive"))
      (node (ref "U$17") (pin "4") (pinfunction "G1_4") (pintype "bidirectional"))
    )
    (net (code "44") (name "Net-(U$17-G2)") (class "Default")
      (node (ref "R4") (pin "2") (pinfunction "2_2") (pintype "passive"))
      (node (ref "R5") (pin "1") (pinfunction "1_1") (pintype "passive"))
      (node (ref "U$17") (pin "5") (pinfunction "G2_5") (pintype "bidirectional"))
    )
    (net (code "45") (name "Net-(U$22-COL1)") (class "Default")
      (node (ref "R5") (pin "2") (pinfunction "2_2") (pintype "passive"))
      (node (ref "U$22") (pin "8") (pinfunction "COL1_8") (pintype "bidirectional"))
    )
    (net (code "46") (name "Net-(U$22-COL2)") (class "Default")
      (node (ref "R3") (pin "2") (pinfunction "2_2") (pintype "passive"))
      (node (ref "U$22") (pin "6") (pinfunction "COL2_6") (pintype "bidirectional"))
    )
    (net (code "47") (name "Net-(U$23-D)") (class "Default")
      (node (ref "R11") (pin "2") (pinfunction "2_2") (pintype "passive"))
      (node (ref "U$23") (pin "3") (pinfunction "D_3") (pintype "bidirectional"))
      (node (ref "U$24") (pin "2") (pinfunction "GND_2") (pintype "bidirectional"))
    )
    (net (code "48") (name "Net-(U$25-D)") (class "Default")
      (node (ref "R19") (pin "2") (pinfunction "2_2") (pintype "passive"))
      (node (ref "U$25") (pin "3") (pinfunction "D_3") (pintype "bidirectional"))
      (node (ref "U$27") (pin "P$1") (pinfunction "P$1_P$1") (pintype "bidirectional"))
      (node (ref "U$28") (pin "P$1") (pinfunction "P$1_P$1") (pintype "bidirectional"))
      (node (ref "U$29") (pin "P$1") (pinfunction "P$1_P$1") (pintype "bidirectional"))
      (node (ref "U$30") (pin "P$1") (pinfunction "P$1_P$1") (pintype "bidirectional"))
    )
  )
)
